# soc-io.net
KiCad netlist of a schematic drawn in Altium Designer
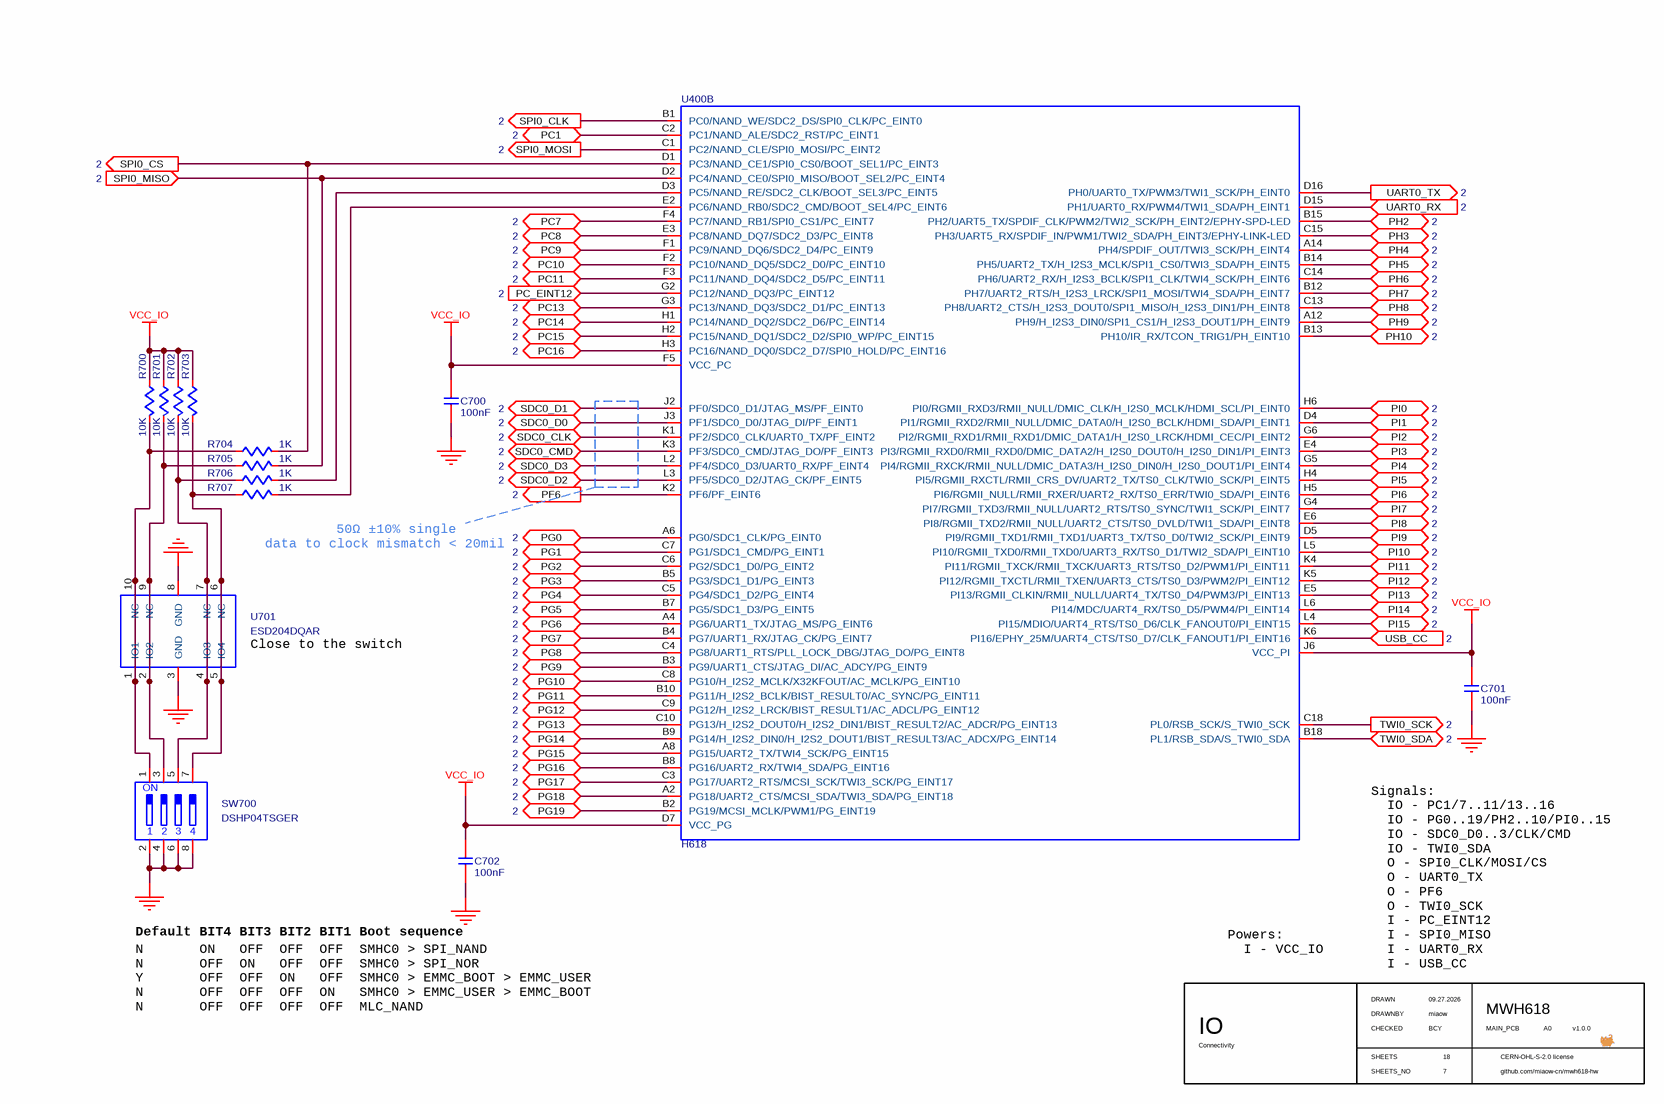
[diagram p0: soc-io.schdoc]

(export (version "E")
  (design (tool "Eeschema 10.0.6"))
  (components
    (comp (ref "C700")
      (value "100nF")
      (footprint "mw:C0201")
      (fields (field (name "VOLTAGE") "10V") (field (name "Comment") "C-NOMO"))
      (libsource (lib "mw") (part "C-NOMO"))
    )
    (comp (ref "C701")
      (value "100nF")
      (footprint "mw:C0201")
      (fields (field (name "VOLTAGE") "10V") (field (name "Comment") "C-NOMO"))
      (libsource (lib "mw") (part "C-NOMO"))
    )
    (comp (ref "C702")
      (value "100nF")
      (footprint "mw:C0201")
      (fields (field (name "VOLTAGE") "10V") (field (name "Comment") "C-NOMO"))
      (libsource (lib "mw") (part "C-NOMO"))
    )
    (comp (ref "R700")
      (value "10K")
      (footprint "mw:R0402")
      (fields (field (name "Comment") "R"))
      (libsource (lib "mw") (part "R"))
    )
    (comp (ref "R701")
      (value "10K")
      (footprint "mw:R0402")
      (fields (field (name "Comment") "R"))
      (libsource (lib "mw") (part "R"))
    )
    (comp (ref "R702")
      (value "10K")
      (footprint "mw:R0402")
      (fields (field (name "Comment") "R"))
      (libsource (lib "mw") (part "R"))
    )
    (comp (ref "R703")
      (value "10K")
      (footprint "mw:R0402")
      (fields (field (name "Comment") "R"))
      (libsource (lib "mw") (part "R"))
    )
    (comp (ref "R704")
      (value "1K")
      (footprint "mw:R0402")
      (fields (field (name "Comment") "R"))
      (libsource (lib "mw") (part "R"))
    )
    (comp (ref "R705")
      (value "1K")
      (footprint "mw:R0402")
      (fields (field (name "Comment") "R"))
      (libsource (lib "mw") (part "R"))
    )
    (comp (ref "R706")
      (value "1K")
      (footprint "mw:R0402")
      (fields (field (name "Comment") "R"))
      (libsource (lib "mw") (part "R"))
    )
    (comp (ref "R707")
      (value "1K")
      (footprint "mw:R0402")
      (fields (field (name "Comment") "R"))
      (libsource (lib "mw") (part "R"))
    )
    (comp (ref "SW700")
      (value "DSHP04TSGER")
      (footprint "mw:DSHP04TSGER")
      (libsource (lib "mw") (part "DSHP04TSGER"))
    )
    (comp (ref "U400")
      (value "H618")
      (footprint "mw:H618")
      (description "SOC")
      (libsource (lib "mw") (part "H618"))
    )
    (comp (ref "U701")
      (value "ESD204DQAR")
      (footprint "mw:ESD204DQAR")
      (description "TVS/ESD - 4 ch, 3.6V, 5V, 0.55pF@1MHz, 30KV")
      (libsource (lib "mw") (part "ESD204DQAR"))
    )
  )
  (nets
    (net (code "1") (name "/PC1") (class "Default")
      (node (ref "U400") (pin "C2") (pinfunction "PC1/NAND_ALE/SDC2_RST/PC_EINT1_C2") (pintype "passive"))
    )
    (net (code "2") (name "/PC7") (class "Default")
      (node (ref "U400") (pin "F4") (pinfunction "PC7/NAND_RB1/SPI0_CS1/PC_EINT7_F4") (pintype "passive"))
    )
    (net (code "3") (name "/PC8") (class "Default")
      (node (ref "U400") (pin "E3") (pinfunction "PC8/NAND_DQ7/SDC2_D3/PC_EINT8_E3") (pintype "passive"))
    )
    (net (code "4") (name "/PC9") (class "Default")
      (node (ref "U400") (pin "F1") (pinfunction "PC9/NAND_DQ6/SDC2_D4/PC_EINT9_F1") (pintype "passive"))
    )
    (net (code "5") (name "/PC10") (class "Default")
      (node (ref "U400") (pin "F2") (pinfunction "PC10/NAND_DQ5/SDC2_D0/PC_EINT10_F2") (pintype "passive"))
    )
    (net (code "6") (name "/PC11") (class "Default")
      (node (ref "U400") (pin "F3") (pinfunction "PC11/NAND_DQ4/SDC2_D5/PC_EINT11_F3") (pintype "passive"))
    )
    (net (code "7") (name "/PC13") (class "Default")
      (node (ref "U400") (pin "G3") (pinfunction "PC13/NAND_DQ3/SDC2_D1/PC_EINT13_G3") (pintype "passive"))
    )
    (net (code "8") (name "/PC14") (class "Default")
      (node (ref "U400") (pin "H1") (pinfunction "PC14/NAND_DQ2/SDC2_D6/PC_EINT14_H1") (pintype "passive"))
    )
    (net (code "9") (name "/PC15") (class "Default")
      (node (ref "U400") (pin "H2") (pinfunction "PC15/NAND_DQ1/SDC2_D2/SPI0_WP/PC_EINT15_H2") (pintype "passive"))
    )
    (net (code "10") (name "/PC16") (class "Default")
      (node (ref "U400") (pin "H3") (pinfunction "PC16/NAND_DQ0/SDC2_D7/SPI0_HOLD/PC_EINT16_H3") (pintype "passive"))
    )
    (net (code "11") (name "/PC_EINT12") (class "Default")
      (node (ref "U400") (pin "G2") (pinfunction "PC12/NAND_DQ3/PC_EINT12_G2") (pintype "passive"))
    )
    (net (code "12") (name "/PF6") (class "Default")
      (node (ref "U400") (pin "K2") (pinfunction "PF6/PF_EINT6_K2") (pintype "passive"))
    )
    (net (code "13") (name "/PG0") (class "Default")
      (node (ref "U400") (pin "A6") (pinfunction "PG0/SDC1_CLK/PG_EINT0_A6") (pintype "passive"))
    )
    (net (code "14") (name "/PG1") (class "Default")
      (node (ref "U400") (pin "C7") (pinfunction "PG1/SDC1_CMD/PG_EINT1_C7") (pintype "passive"))
    )
    (net (code "15") (name "/PG2") (class "Default")
      (node (ref "U400") (pin "C6") (pinfunction "PG2/SDC1_D0/PG_EINT2_C6") (pintype "passive"))
    )
    (net (code "16") (name "/PG3") (class "Default")
      (node (ref "U400") (pin "B5") (pinfunction "PG3/SDC1_D1/PG_EINT3_B5") (pintype "passive"))
    )
    (net (code "17") (name "/PG4") (class "Default")
      (node (ref "U400") (pin "C5") (pinfunction "PG4/SDC1_D2/PG_EINT4_C5") (pintype "passive"))
    )
    (net (code "18") (name "/PG5") (class "Default")
      (node (ref "U400") (pin "B7") (pinfunction "PG5/SDC1_D3/PG_EINT5_B7") (pintype "passive"))
    )
    (net (code "19") (name "/PG6") (class "Default")
      (node (ref "U400") (pin "A4") (pinfunction "PG6/UART1_TX/JTAG_MS/PG_EINT6_A4") (pintype "passive"))
    )
    (net (code "20") (name "/PG7") (class "Default")
      (node (ref "U400") (pin "B4") (pinfunction "PG7/UART1_RX/JTAG_CK/PG_EINT7_B4") (pintype "passive"))
    )
    (net (code "21") (name "/PG8") (class "Default")
      (node (ref "U400") (pin "C4") (pinfunction "PG8/UART1_RTS/PLL_LOCK_DBG/JTAG_DO/PG_EINT8_C4") (pintype "passive"))
    )
    (net (code "22") (name "/PG9") (class "Default")
      (node (ref "U400") (pin "B3") (pinfunction "PG9/UART1_CTS/JTAG_DI/AC_ADCY/PG_EINT9_B3") (pintype "passive"))
    )
    (net (code "23") (name "/PG10") (class "Default")
      (node (ref "U400") (pin "C8") (pinfunction "PG10/H_I2S2_MCLK/X32KFOUT/AC_MCLK/PG_EINT10_C8") (pintype "passive"))
    )
    (net (code "24") (name "/PG11") (class "Default")
      (node (ref "U400") (pin "B10") (pinfunction "PG11/H_I2S2_BCLK/BIST_RESULT0/AC_SYNC/PG_EINT11_B10") (pintype "passive"))
    )
    (net (code "25") (name "/PG12") (class "Default")
      (node (ref "U400") (pin "C9") (pinfunction "PG12/H_I2S2_LRCK/BIST_RESULT1/AC_ADCL/PG_EINT12_C9") (pintype "passive"))
    )
    (net (code "26") (name "/PG13") (class "Default")
      (node (ref "U400") (pin "C10") (pinfunction "PG13/H_I2S2_DOUT0/H_I2S2_DIN1/BIST_RESULT2/AC_ADCR/PG_EINT13_C10") (pintype "passive"))
    )
    (net (code "27") (name "/PG14") (class "Default")
      (node (ref "U400") (pin "B9") (pinfunction "PG14/H_I2S2_DIN0/H_I2S2_DOUT1/BIST_RESULT3/AC_ADCX/PG_EINT14_B9") (pintype "passive"))
    )
    (net (code "28") (name "/PG15") (class "Default")
      (node (ref "U400") (pin "A8") (pinfunction "PG15/UART2_TX/TWI4_SCK/PG_EINT15_A8") (pintype "passive"))
    )
    (net (code "29") (name "/PG16") (class "Default")
      (node (ref "U400") (pin "B8") (pinfunction "PG16/UART2_RX/TWI4_SDA/PG_EINT16_B8") (pintype "passive"))
    )
    (net (code "30") (name "/PG17") (class "Default")
      (node (ref "U400") (pin "C3") (pinfunction "PG17/UART2_RTS/MCSI_SCK/TWI3_SCK/PG_EINT17_C3") (pintype "passive"))
    )
    (net (code "31") (name "/PG18") (class "Default")
      (node (ref "U400") (pin "A2") (pinfunction "PG18/UART2_CTS/MCSI_SDA/TWI3_SDA/PG_EINT18_A2") (pintype "passive"))
    )
    (net (code "32") (name "/PG19") (class "Default")
      (node (ref "U400") (pin "B2") (pinfunction "PG19/MCSI_MCLK/PWM1/PG_EINT19_B2") (pintype "passive"))
    )
    (net (code "33") (name "/PH2") (class "Default")
      (node (ref "U400") (pin "B15") (pinfunction "PH2/UART5_TX/SPDIF_CLK/PWM2/TWI2_SCK/PH_EINT2/EPHY-SPD-LED_B15") (pintype "passive"))
    )
    (net (code "34") (name "/PH3") (class "Default")
      (node (ref "U400") (pin "C15") (pinfunction "PH3/UART5_RX/SPDIF_IN/PWM1/TWI2_SDA/PH_EINT3/EPHY-LINK-LED_C15") (pintype "passive"))
    )
    (net (code "35") (name "/PH4") (class "Default")
      (node (ref "U400") (pin "A14") (pinfunction "PH4/SPDIF_OUT/TWI3_SCK/PH_EINT4_A14") (pintype "passive"))
    )
    (net (code "36") (name "/PH5") (class "Default")
      (node (ref "U400") (pin "B14") (pinfunction "PH5/UART2_TX/H_I2S3_MCLK/SPI1_CS0/TWI3_SDA/PH_EINT5_B14") (pintype "passive"))
    )
    (net (code "37") (name "/PH6") (class "Default")
      (node (ref "U400") (pin "C14") (pinfunction "PH6/UART2_RX/H_I2S3_BCLK/SPI1_CLK/TWI4_SCK/PH_EINT6_C14") (pintype "passive"))
    )
    (net (code "38") (name "/PH7") (class "Default")
      (node (ref "U400") (pin "B12") (pinfunction "PH7/UART2_RTS/H_I2S3_LRCK/SPI1_MOSI/TWI4_SDA/PH_EINT7_B12") (pintype "passive"))
    )
    (net (code "39") (name "/PH8") (class "Default")
      (node (ref "U400") (pin "C13") (pinfunction "PH8/UART2_CTS/H_I2S3_DOUT0/SPI1_MISO/H_I2S3_DIN1/PH_EINT8_C13") (pintype "passive"))
    )
    (net (code "40") (name "/PH9") (class "Default")
      (node (ref "U400") (pin "A12") (pinfunction "PH9/H_I2S3_DIN0/SPI1_CS1/H_I2S3_DOUT1/PH_EINT9_A12") (pintype "passive"))
    )
    (net (code "41") (name "/PH10") (class "Default")
      (node (ref "U400") (pin "B13") (pinfunction "PH10/IR_RX/TCON_TRIG1/PH_EINT10_B13") (pintype "passive"))
    )
    (net (code "42") (name "/PI0") (class "Default")
      (node (ref "U400") (pin "H6") (pinfunction "PI0/RGMII_RXD3/RMII_NULL/DMIC_CLK/H_I2S0_MCLK/HDMI_SCL/PI_EINT0_H6") (pintype "passive"))
    )
    (net (code "43") (name "/PI1") (class "Default")
      (node (ref "U400") (pin "D4") (pinfunction "PI1/RGMII_RXD2/RMII_NULL/DMIC_DATA0/H_I2S0_BCLK/HDMI_SDA/PI_EINT1_D4") (pintype "passive"))
    )
    (net (code "44") (name "/PI2") (class "Default")
      (node (ref "U400") (pin "G6") (pinfunction "PI2/RGMII_RXD1/RMII_RXD1/DMIC_DATA1/H_I2S0_LRCK/HDMI_CEC/PI_EINT2_G6") (pintype "passive"))
    )
    (net (code "45") (name "/PI3") (class "Default")
      (node (ref "U400") (pin "E4") (pinfunction "PI3/RGMII_RXD0/RMII_RXD0/DMIC_DATA2/H_I2S0_DOUT0/H_I2S0_DIN1/PI_EINT3_E4") (pintype "passive"))
    )
    (net (code "46") (name "/PI4") (class "Default")
      (node (ref "U400") (pin "G5") (pinfunction "PI4/RGMII_RXCK/RMII_NULL/DMIC_DATA3/H_I2S0_DIN0/H_I2S0_DOUT1/PI_EINT4_G5") (pintype "passive"))
    )
    (net (code "47") (name "/PI5") (class "Default")
      (node (ref "U400") (pin "H4") (pinfunction "PI5/RGMII_RXCTL/RMII_CRS_DV/UART2_TX/TS0_CLK/TWI0_SCK/PI_EINT5_H4") (pintype "passive"))
    )
    (net (code "48") (name "/PI6") (class "Default")
      (node (ref "U400") (pin "H5") (pinfunction "PI6/RGMII_NULL/RMII_RXER/UART2_RX/TS0_ERR/TWI0_SDA/PI_EINT6_H5") (pintype "passive"))
    )
    (net (code "49") (name "/PI7") (class "Default")
      (node (ref "U400") (pin "G4") (pinfunction "PI7/RGMII_TXD3/RMII_NULL/UART2_RTS/TS0_SYNC/TWI1_SCK/PI_EINT7_G4") (pintype "passive"))
    )
    (net (code "50") (name "/PI8") (class "Default")
      (node (ref "U400") (pin "E6") (pinfunction "PI8/RGMII_TXD2/RMII_NULL/UART2_CTS/TS0_DVLD/TWI1_SDA/PI_EINT8_E6") (pintype "passive"))
    )
    (net (code "51") (name "/PI9") (class "Default")
      (node (ref "U400") (pin "D5") (pinfunction "PI9/RGMII_TXD1/RMII_TXD1/UART3_TX/TS0_D0/TWI2_SCK/PI_EINT9_D5") (pintype "passive"))
    )
    (net (code "52") (name "/PI10") (class "Default")
      (node (ref "U400") (pin "L5") (pinfunction "PI10/RGMII_TXD0/RMII_TXD0/UART3_RX/TS0_D1/TWI2_SDA/PI_EINT10_L5") (pintype "passive"))
    )
    (net (code "53") (name "/PI11") (class "Default")
      (node (ref "U400") (pin "K4") (pinfunction "PI11/RGMII_TXCK/RMII_TXCK/UART3_RTS/TS0_D2/PWM1/PI_EINT11_K4") (pintype "passive"))
    )
    (net (code "54") (name "/PI12") (class "Default")
      (node (ref "U400") (pin "K5") (pinfunction "PI12/RGMII_TXCTL/RMII_TXEN/UART3_CTS/TS0_D3/PWM2/PI_EINT12_K5") (pintype "passive"))
    )
    (net (code "55") (name "/PI13") (class "Default")
      (node (ref "U400") (pin "E5") (pinfunction "PI13/RGMII_CLKIN/RMII_NULL/UART4_TX/TS0_D4/PWM3/PI_EINT13_E5") (pintype "passive"))
    )
    (net (code "56") (name "/PI14") (class "Default")
      (node (ref "U400") (pin "L6") (pinfunction "PI14/MDC/UART4_RX/TS0_D5/PWM4/PI_EINT14_L6") (pintype "passive"))
    )
    (net (code "57") (name "/PI15") (class "Default")
      (node (ref "U400") (pin "L4") (pinfunction "PI15/MDIO/UART4_RTS/TS0_D6/CLK_FANOUT0/PI_EINT15_L4") (pintype "passive"))
    )
    (net (code "58") (name "/SDC0_CLK") (class "Default")
      (node (ref "U400") (pin "K1") (pinfunction "PF2/SDC0_CLK/UART0_TX/PF_EINT2_K1") (pintype "passive"))
    )
    (net (code "59") (name "/SDC0_CMD") (class "Default")
      (node (ref "U400") (pin "K3") (pinfunction "PF3/SDC0_CMD/JTAG_DO/PF_EINT3_K3") (pintype "passive"))
    )
    (net (code "60") (name "/SDC0_D0") (class "Default")
      (node (ref "U400") (pin "J3") (pinfunction "PF1/SDC0_D0/JTAG_DI/PF_EINT1_J3") (pintype "passive"))
    )
    (net (code "61") (name "/SDC0_D1") (class "Default")
      (node (ref "U400") (pin "J2") (pinfunction "PF0/SDC0_D1/JTAG_MS/PF_EINT0_J2") (pintype "passive"))
    )
    (net (code "62") (name "/SDC0_D2") (class "Default")
      (node (ref "U400") (pin "L3") (pinfunction "PF5/SDC0_D2/JTAG_CK/PF_EINT5_L3") (pintype "passive"))
    )
    (net (code "63") (name "/SDC0_D3") (class "Default")
      (node (ref "U400") (pin "L2") (pinfunction "PF4/SDC0_D3/UART0_RX/PF_EINT4_L2") (pintype "passive"))
    )
    (net (code "64") (name "/SPI0_CLK") (class "Default")
      (node (ref "U400") (pin "B1") (pinfunction "PC0/NAND_WE/SDC2_DS/SPI0_CLK/PC_EINT0_B1") (pintype "passive"))
    )
    (net (code "65") (name "/SPI0_CS") (class "Default")
      (node (ref "R704") (pin "1") (pinfunction "1_1") (pintype "passive"))
      (node (ref "U400") (pin "D1") (pinfunction "PC3/NAND_CE1/SPI0_CS0/BOOT_SEL1/PC_EINT3_D1") (pintype "passive"))
    )
    (net (code "66") (name "/SPI0_MISO") (class "Default")
      (node (ref "R705") (pin "1") (pinfunction "1_1") (pintype "passive"))
      (node (ref "U400") (pin "D2") (pinfunction "PC4/NAND_CE0/SPI0_MISO/BOOT_SEL2/PC_EINT4_D2") (pintype "passive"))
    )
    (net (code "67") (name "/SPI0_MOSI") (class "Default")
      (node (ref "U400") (pin "C1") (pinfunction "PC2/NAND_CLE/SPI0_MOSI/PC_EINT2_C1") (pintype "passive"))
    )
    (net (code "68") (name "/TWI0_SCK") (class "Default")
      (node (ref "U400") (pin "C18") (pinfunction "PL0/RSB_SCK/S_TWI0_SCK_C18") (pintype "passive"))
    )
    (net (code "69") (name "/TWI0_SDA") (class "Default")
      (node (ref "U400") (pin "B18") (pinfunction "PL1/RSB_SDA/S_TWI0_SDA_B18") (pintype "passive"))
    )
    (net (code "70") (name "/UART0_RX") (class "Default")
      (node (ref "U400") (pin "D15") (pinfunction "PH1/UART0_RX/PWM4/TWI1_SDA/PH_EINT1_D15") (pintype "passive"))
    )
    (net (code "71") (name "/UART0_TX") (class "Default")
      (node (ref "U400") (pin "D16") (pinfunction "PH0/UART0_TX/PWM3/TWI1_SCK/PH_EINT0_D16") (pintype "passive"))
    )
    (net (code "72") (name "/USB_CC") (class "Default")
      (node (ref "U400") (pin "K6") (pinfunction "PI16/EPHY_25M/UART4_CTS/TS0_D7/CLK_FANOUT1/PI_EINT16_K6") (pintype "passive"))
    )
    (net (code "73") (name "GND") (class "Default")
      (node (ref "C700") (pin "2") (pinfunction "2_2") (pintype "passive"))
      (node (ref "C701") (pin "2") (pinfunction "2_2") (pintype "passive"))
      (node (ref "C702") (pin "2") (pinfunction "2_2") (pintype "passive"))
      (node (ref "SW700") (pin "2") (pinfunction "2_2") (pintype "passive"))
      (node (ref "SW700") (pin "4") (pinfunction "4_4") (pintype "passive"))
      (node (ref "SW700") (pin "6") (pinfunction "6_6") (pintype "passive"))
      (node (ref "SW700") (pin "8") (pinfunction "8_8") (pintype "passive"))
      (node (ref "U701") (pin "3") (pinfunction "GND_3") (pintype "passive"))
      (node (ref "U701") (pin "8") (pinfunction "GND_8") (pintype "passive"))
    )
    (net (code "74") (name "Net-(U400B-PC5{slash}NAND_RE{slash}SDC2_CLK{slash}BOOT_SEL3{slash}PC_EINT5)") (class "Default")
      (node (ref "R706") (pin "1") (pinfunction "1_1") (pintype "passive"))
      (node (ref "U400") (pin "D3") (pinfunction "PC5/NAND_RE/SDC2_CLK/BOOT_SEL3/PC_EINT5_D3") (pintype "passive"))
    )
    (net (code "75") (name "Net-(U400B-PC6{slash}NAND_RB0{slash}SDC2_CMD{slash}BOOT_SEL4{slash}PC_EINT6)") (class "Default")
      (node (ref "R707") (pin "1") (pinfunction "1_1") (pintype "passive"))
      (node (ref "U400") (pin "E2") (pinfunction "PC6/NAND_RB0/SDC2_CMD/BOOT_SEL4/PC_EINT6_E2") (pintype "passive"))
    )
    (net (code "76") (name "Net-(U701-IO1)") (class "Default")
      (node (ref "R700") (pin "1") (pinfunction "1_1") (pintype "passive"))
      (node (ref "R704") (pin "2") (pinfunction "2_2") (pintype "passive"))
      (node (ref "SW700") (pin "1") (pinfunction "1_1") (pintype "passive"))
      (node (ref "U701") (pin "1") (pinfunction "IO1_1") (pintype "passive"))
      (node (ref "U701") (pin "10") (pinfunction "NC_10") (pintype "passive"))
    )
    (net (code "77") (name "Net-(U701-IO2)") (class "Default")
      (node (ref "R701") (pin "1") (pinfunction "1_1") (pintype "passive"))
      (node (ref "R705") (pin "2") (pinfunction "2_2") (pintype "passive"))
      (node (ref "SW700") (pin "3") (pinfunction "3_3") (pintype "passive"))
      (node (ref "U701") (pin "2") (pinfunction "IO2_2") (pintype "passive"))
      (node (ref "U701") (pin "9") (pinfunction "NC_9") (pintype "passive"))
    )
    (net (code "78") (name "Net-(U701-IO3)") (class "Default")
      (node (ref "R702") (pin "1") (pinfunction "1_1") (pintype "passive"))
      (node (ref "R706") (pin "2") (pinfunction "2_2") (pintype "passive"))
      (node (ref "SW700") (pin "5") (pinfunction "5_5") (pintype "passive"))
      (node (ref "U701") (pin "4") (pinfunction "IO3_4") (pintype "passive"))
      (node (ref "U701") (pin "7") (pinfunction "NC_7") (pintype "passive"))
    )
    (net (code "79") (name "Net-(U701-IO4)") (class "Default")
      (node (ref "R703") (pin "1") (pinfunction "1_1") (pintype "passive"))
      (node (ref "R707") (pin "2") (pinfunction "2_2") (pintype "passive"))
      (node (ref "SW700") (pin "7") (pinfunction "7_7") (pintype "passive"))
      (node (ref "U701") (pin "5") (pinfunction "IO4_5") (pintype "passive"))
      (node (ref "U701") (pin "6") (pinfunction "NC_6") (pintype "passive"))
    )
    (net (code "80") (name "VCC_IO") (class "Default")
      (node (ref "C700") (pin "1") (pinfunction "1_1") (pintype "passive"))
      (node (ref "C701") (pin "1") (pinfunction "1_1") (pintype "passive"))
      (node (ref "C702") (pin "1") (pinfunction "1_1") (pintype "passive"))
      (node (ref "R700") (pin "2") (pinfunction "2_2") (pintype "passive"))
      (node (ref "R701") (pin "2") (pinfunction "2_2") (pintype "passive"))
      (node (ref "R702") (pin "2") (pinfunction "2_2") (pintype "passive"))
      (node (ref "R703") (pin "2") (pinfunction "2_2") (pintype "passive"))
      (node (ref "U400") (pin "D7") (pinfunction "VCC_PG_D7") (pintype "passive"))
      (node (ref "U400") (pin "F5") (pinfunction "VCC_PC_F5") (pintype "passive"))
      (node (ref "U400") (pin "J6") (pinfunction "VCC_PI_J6") (pintype "passive"))
    )
  )
)
